# RS485.net
KiCad netlist of a schematic drawn in Altium Designer
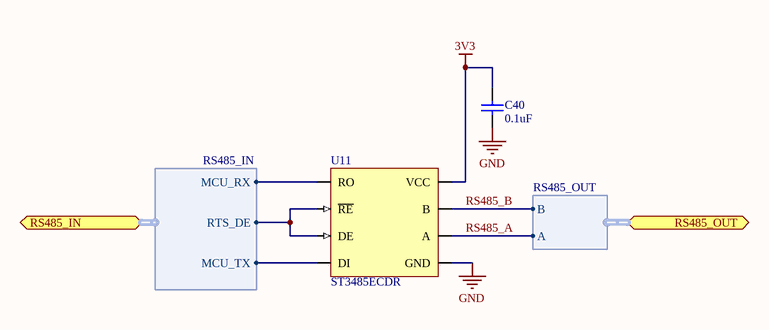
[diagram p0: RS485.SchDoc]

(export (version "E")
  (design (tool "Eeschema 10.0.6"))
  (components
    (comp (ref "C40")
      (value "0.1uF")
      (footprint "CAPC0603(1608)100_L")
      (description "CAP 100nF 100V ±10% 0603 (1608 Metric) Thickness 1mm SMD")
      (fields (field (name "TOLERANCE") "Â±10%"))
      (libsource (lib "Altium Content Vault") (part "CMP-1035-02595-1"))
    )
    (comp (ref "U11")
      (value "ST3485ECDR")
      (footprint "SOIC-8")
      (description "3.3 V powered, 15 kV ESD protected, up to 12 Mbps RS-485/  RS-422 transceiver 0 to 70")
      (fields (field (name "MANUFACTURER") "STMicroelectronics"))
      (libsource (lib "ICs") (part "ST3485ECDR"))
    )
  )
  (nets
    (net (code "3") (name "/MCU_RX") (class "Default")
      (node (ref "U11") (pin "1") (pinfunction "RO_1") (pintype "bidirectional"))
    )
    (net (code "4") (name "/MCU_TX") (class "Default")
      (node (ref "U11") (pin "4") (pinfunction "DI_4") (pintype "bidirectional"))
    )
    (net (code "5") (name "/RS485_A") (class "Default")
      (node (ref "U11") (pin "6") (pinfunction "A_6") (pintype "bidirectional"))
    )
    (net (code "6") (name "/RS485_B") (class "Default")
      (node (ref "U11") (pin "7") (pinfunction "B_7") (pintype "bidirectional"))
    )
    (net (code "7") (name "/RTS_DE") (class "Default")
      (node (ref "U11") (pin "2") (pinfunction "~{RE}_2") (pintype "input"))
      (node (ref "U11") (pin "3") (pinfunction "DE_3") (pintype "input"))
    )
    (net (code "10") (name "3V3") (class "Default")
      (node (ref "C40") (pin "2") (pinfunction "2_2") (pintype "passive"))
      (node (ref "U11") (pin "8") (pinfunction "VCC_8") (pintype "power_in"))
    )
    (net (code "11") (name "GND") (class "Default")
      (node (ref "C40") (pin "1") (pinfunction "1_1") (pintype "passive"))
      (node (ref "U11") (pin "5") (pinfunction "GND_5") (pintype "power_in"))
    )
  )
)
